# GM-UART-V1.net
KiCad netlist of a schematic drawn in EAGLE
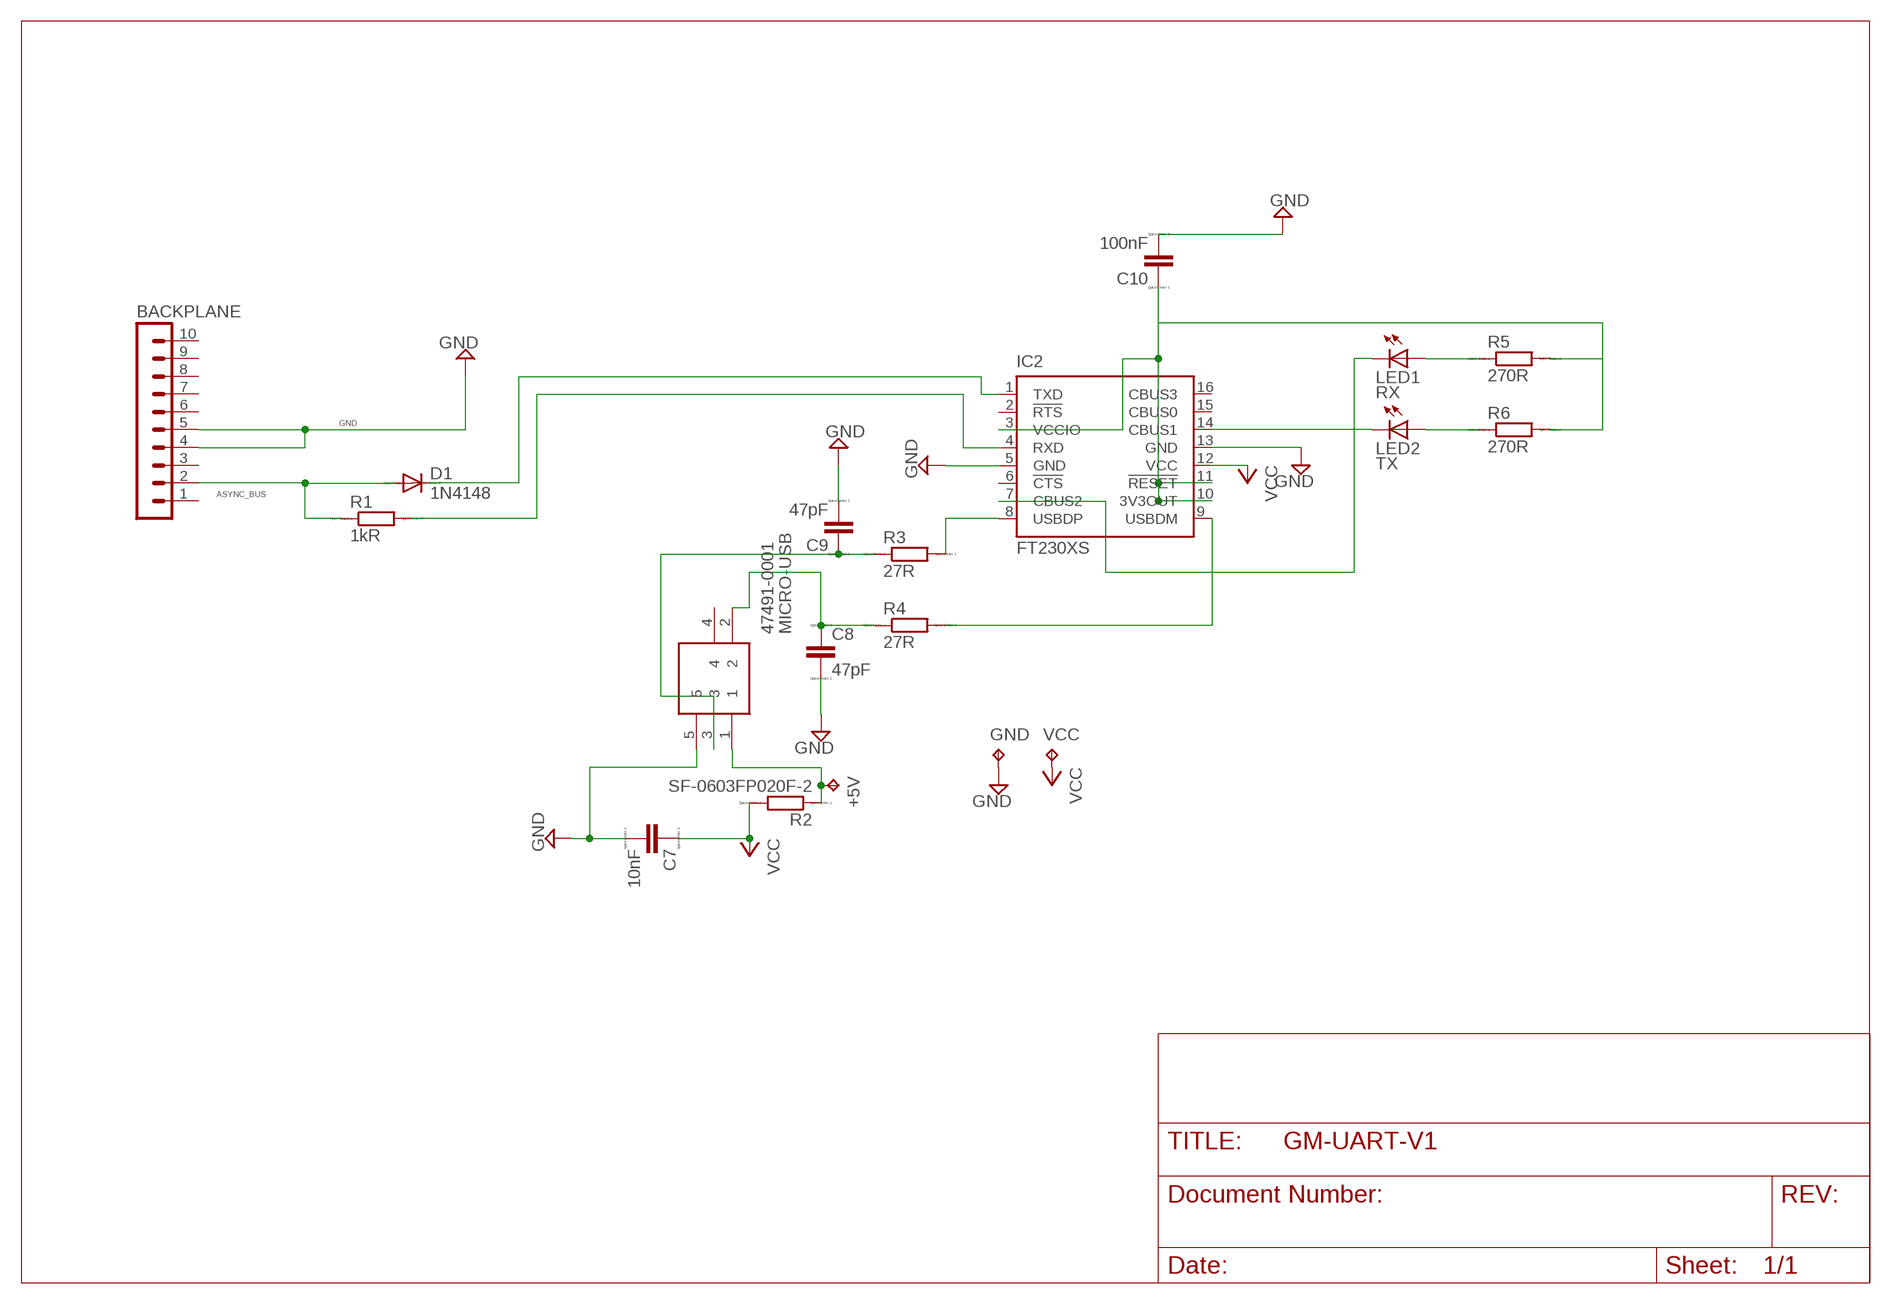
[diagram p0: schematic, sheet 1]

(export (version "E")
  (design (tool "Eeschema 10.0.6"))
  (components
    (comp (ref "+5V")
      (value "VCC-Unfused")
      (footprint "eagle-import:TP14SQ")
      (libsource (lib "eagle-import") (part "TPTP14SQ"))
    )
    (comp (ref "BACKPLANE")
      (value "MA10-1")
      (footprint "eagle-import:MA10-1")
      (libsource (lib "eagle-import") (part "MA10-1"))
    )
    (comp (ref "C7")
      (value "10nF")
      (footprint "eagle-import:C0402")
      (libsource (lib "eagle-import") (part "CC0402"))
    )
    (comp (ref "C8")
      (value "47pF")
      (footprint "eagle-import:C0402")
      (libsource (lib "eagle-import") (part "CC0402"))
    )
    (comp (ref "C9")
      (value "47pF")
      (footprint "eagle-import:C0402")
      (libsource (lib "eagle-import") (part "CC0402"))
    )
    (comp (ref "C10")
      (value "100nF")
      (footprint "eagle-import:C0402")
      (libsource (lib "eagle-import") (part "CC0402"))
    )
    (comp (ref "D1")
      (value "1N4148")
      (footprint "eagle-import:SOD523")
      (libsource (lib "eagle-import") (part "DIODE-SOD523"))
    )
    (comp (ref "GND")
      (value "TPTP14SQ")
      (footprint "eagle-import:TP14SQ")
      (libsource (lib "eagle-import") (part "TPTP14SQ"))
    )
    (comp (ref "IC2")
      (value "FT230XS")
      (footprint "eagle-import:SSOP16")
      (libsource (lib "eagle-import") (part "FT230XS"))
    )
    (comp (ref "LED1")
      (value "RX")
      (footprint "eagle-import:LED3MM")
      (fields (field (name "MF") "VISHAY SEMICONDUCTOR"))
      (libsource (lib "eagle-import") (part "TLLG4400"))
    )
    (comp (ref "LED2")
      (value "TX")
      (footprint "eagle-import:LED3MM")
      (fields (field (name "MF") "VISHAY SEMICONDUCTOR"))
      (libsource (lib "eagle-import") (part "TLLR4400"))
    )
    (comp (ref "MICRO-USB")
      (value "47491-0001")
      (footprint "eagle-import:47491-0001")
      (fields (field (name "MOUSER_PART_NUMBER") "538-47491-0001") (field (name "RS_PART_NUMBER") "7025479P"))
      (libsource (lib "eagle-import") (part "47491-0001"))
    )
    (comp (ref "R1")
      (value "1kR")
      (footprint "eagle-import:R0402")
      (libsource (lib "eagle-import") (part "RR0402"))
    )
    (comp (ref "R2")
      (value "SF-0603FP020F-2")
      (footprint "eagle-import:R0603")
      (libsource (lib "eagle-import") (part "RR0603"))
    )
    (comp (ref "R3")
      (value "27R")
      (footprint "eagle-import:R0402")
      (libsource (lib "eagle-import") (part "RR0402"))
    )
    (comp (ref "R4")
      (value "27R")
      (footprint "eagle-import:R0402")
      (libsource (lib "eagle-import") (part "RR0402"))
    )
    (comp (ref "R5")
      (value "270R")
      (footprint "eagle-import:0207_10")
      (libsource (lib "eagle-import") (part "R0207/10"))
    )
    (comp (ref "R6")
      (value "270R")
      (footprint "eagle-import:0207_10")
      (libsource (lib "eagle-import") (part "R0207/10"))
    )
    (comp (ref "VCC")
      (value "VCC-Fused")
      (footprint "eagle-import:TP14SQ")
      (libsource (lib "eagle-import") (part "TPTP14SQ"))
    )
  )
  (nets
    (net (code "1") (name "/ASYNC_BUS") (class "Default")
      (node (ref "BACKPLANE") (pin "2") (pinfunction "2_2") (pintype "passive"))
      (node (ref "D1") (pin "A") (pinfunction "A_A") (pintype "passive"))
      (node (ref "R1") (pin "1") (pinfunction "1_1") (pintype "passive"))
    )
    (net (code "2") (name "GND") (class "Default")
      (node (ref "BACKPLANE") (pin "4") (pinfunction "4_4") (pintype "passive"))
      (node (ref "BACKPLANE") (pin "5") (pinfunction "5_5") (pintype "passive"))
      (node (ref "C10") (pin "2") (pinfunction "2_2") (pintype "passive"))
      (node (ref "C7") (pin "2") (pinfunction "2_2") (pintype "passive"))
      (node (ref "C8") (pin "2") (pinfunction "2_2") (pintype "passive"))
      (node (ref "C9") (pin "2") (pinfunction "2_2") (pintype "passive"))
      (node (ref "GND") (pin "TP") (pinfunction "TP_TP") (pintype "input"))
      (node (ref "IC2") (pin "13") (pinfunction "GND_13") (pintype "power_in"))
      (node (ref "IC2") (pin "5") (pinfunction "GND_5") (pintype "power_in"))
      (node (ref "MICRO-USB") (pin "5") (pinfunction "5_5") (pintype "bidirectional"))
    )
    (net (code "3") (name "Net-(+5V-PadTP)") (class "Default")
      (node (ref "+5V") (pin "TP") (pinfunction "TP_TP") (pintype "input"))
      (node (ref "MICRO-USB") (pin "1") (pinfunction "1_1") (pintype "bidirectional"))
      (node (ref "R2") (pin "1") (pinfunction "1_1") (pintype "passive"))
    )
    (net (code "4") (name "Net-(C8-Pad1)") (class "Default")
      (node (ref "C8") (pin "1") (pinfunction "1_1") (pintype "passive"))
      (node (ref "MICRO-USB") (pin "2") (pinfunction "2_2") (pintype "bidirectional"))
      (node (ref "R4") (pin "1") (pinfunction "1_1") (pintype "passive"))
    )
    (net (code "5") (name "Net-(C9-Pad1)") (class "Default")
      (node (ref "C9") (pin "1") (pinfunction "1_1") (pintype "passive"))
      (node (ref "MICRO-USB") (pin "3") (pinfunction "3_3") (pintype "bidirectional"))
      (node (ref "R3") (pin "1") (pinfunction "1_1") (pintype "passive"))
    )
    (net (code "6") (name "Net-(IC2-3V3OUT)") (class "Default")
      (node (ref "C10") (pin "1") (pinfunction "1_1") (pintype "passive"))
      (node (ref "IC2") (pin "10") (pinfunction "3V3OUT_10") (pintype "output"))
      (node (ref "IC2") (pin "11") (pinfunction "~{RESET}_11") (pintype "input"))
      (node (ref "IC2") (pin "3") (pinfunction "VCCIO_3") (pintype "power_in"))
      (node (ref "R5") (pin "2") (pinfunction "2_2") (pintype "passive"))
      (node (ref "R6") (pin "2") (pinfunction "2_2") (pintype "passive"))
    )
    (net (code "7") (name "Net-(IC2-CBUS1)") (class "Default")
      (node (ref "IC2") (pin "14") (pinfunction "CBUS1_14") (pintype "bidirectional"))
      (node (ref "LED2") (pin "K") (pinfunction "C_K") (pintype "passive"))
    )
    (net (code "8") (name "Net-(IC2-CBUS2)") (class "Default")
      (node (ref "IC2") (pin "7") (pinfunction "CBUS2_7") (pintype "bidirectional"))
      (node (ref "LED1") (pin "K") (pinfunction "C_K") (pintype "passive"))
    )
    (net (code "9") (name "Net-(IC2-RXD)") (class "Default")
      (node (ref "IC2") (pin "4") (pinfunction "RXD_4") (pintype "input"))
      (node (ref "R1") (pin "2") (pinfunction "2_2") (pintype "passive"))
    )
    (net (code "10") (name "Net-(IC2-TXD)") (class "Default")
      (node (ref "D1") (pin "C") (pinfunction "C_C") (pintype "passive"))
      (node (ref "IC2") (pin "1") (pinfunction "TXD_1") (pintype "output"))
    )
    (net (code "11") (name "Net-(IC2-USBDM)") (class "Default")
      (node (ref "IC2") (pin "9") (pinfunction "USBDM_9") (pintype "input"))
      (node (ref "R4") (pin "2") (pinfunction "2_2") (pintype "passive"))
    )
    (net (code "12") (name "Net-(IC2-USBDP)") (class "Default")
      (node (ref "IC2") (pin "8") (pinfunction "USBDP_8") (pintype "input"))
      (node (ref "R3") (pin "2") (pinfunction "2_2") (pintype "passive"))
    )
    (net (code "13") (name "Net-(LED1-PadA)") (class "Default")
      (node (ref "LED1") (pin "A") (pinfunction "A_A") (pintype "passive"))
      (node (ref "R5") (pin "1") (pinfunction "1_1") (pintype "passive"))
    )
    (net (code "14") (name "Net-(LED2-PadA)") (class "Default")
      (node (ref "LED2") (pin "A") (pinfunction "A_A") (pintype "passive"))
      (node (ref "R6") (pin "1") (pinfunction "1_1") (pintype "passive"))
    )
    (net (code "15") (name "VCC") (class "Default")
      (node (ref "C7") (pin "1") (pinfunction "1_1") (pintype "passive"))
      (node (ref "IC2") (pin "12") (pinfunction "VCC_12") (pintype "power_in"))
      (node (ref "R2") (pin "2") (pinfunction "2_2") (pintype "passive"))
      (node (ref "VCC") (pin "TP") (pinfunction "TP_TP") (pintype "input"))
    )
    (net (code "16") (name "unconnected-(BACKPLANE-Pad1)") (class "Default")
      (node (ref "BACKPLANE") (pin "1") (pinfunction "1_1") (pintype "passive"))
    )
    (net (code "17") (name "unconnected-(BACKPLANE-Pad3)") (class "Default")
      (node (ref "BACKPLANE") (pin "3") (pinfunction "3_3") (pintype "passive"))
    )
    (net (code "18") (name "unconnected-(BACKPLANE-Pad6)") (class "Default")
      (node (ref "BACKPLANE") (pin "6") (pinfunction "6_6") (pintype "passive"))
    )
    (net (code "19") (name "unconnected-(BACKPLANE-Pad7)") (class "Default")
      (node (ref "BACKPLANE") (pin "7") (pinfunction "7_7") (pintype "passive"))
    )
    (net (code "20") (name "unconnected-(BACKPLANE-Pad8)") (class "Default")
      (node (ref "BACKPLANE") (pin "8") (pinfunction "8_8") (pintype "passive"))
    )
    (net (code "21") (name "unconnected-(BACKPLANE-Pad9)") (class "Default")
      (node (ref "BACKPLANE") (pin "9") (pinfunction "9_9") (pintype "passive"))
    )
    (net (code "22") (name "unconnected-(BACKPLANE-Pad10)") (class "Default")
      (node (ref "BACKPLANE") (pin "10") (pinfunction "10_10") (pintype "passive"))
    )
    (net (code "23") (name "unconnected-(IC2-CBUS0-Pad15)") (class "Default")
      (node (ref "IC2") (pin "15") (pinfunction "CBUS0_15") (pintype "bidirectional"))
    )
    (net (code "24") (name "unconnected-(IC2-CBUS3-Pad16)") (class "Default")
      (node (ref "IC2") (pin "16") (pinfunction "CBUS3_16") (pintype "bidirectional"))
    )
    (net (code "25") (name "unconnected-(IC2-~{CTS}-Pad6)") (class "Default")
      (node (ref "IC2") (pin "6") (pinfunction "~{CTS}_6") (pintype "input"))
    )
    (net (code "26") (name "unconnected-(IC2-~{RTS}-Pad2)") (class "Default")
      (node (ref "IC2") (pin "2") (pinfunction "~{RTS}_2") (pintype "output"))
    )
    (net (code "27") (name "unconnected-(MICRO-USB-Pad4)") (class "Default")
      (node (ref "MICRO-USB") (pin "4") (pinfunction "4_4") (pintype "bidirectional"))
    )
  )
)
